# controller10.net
KiCad netlist of a schematic drawn in EAGLE
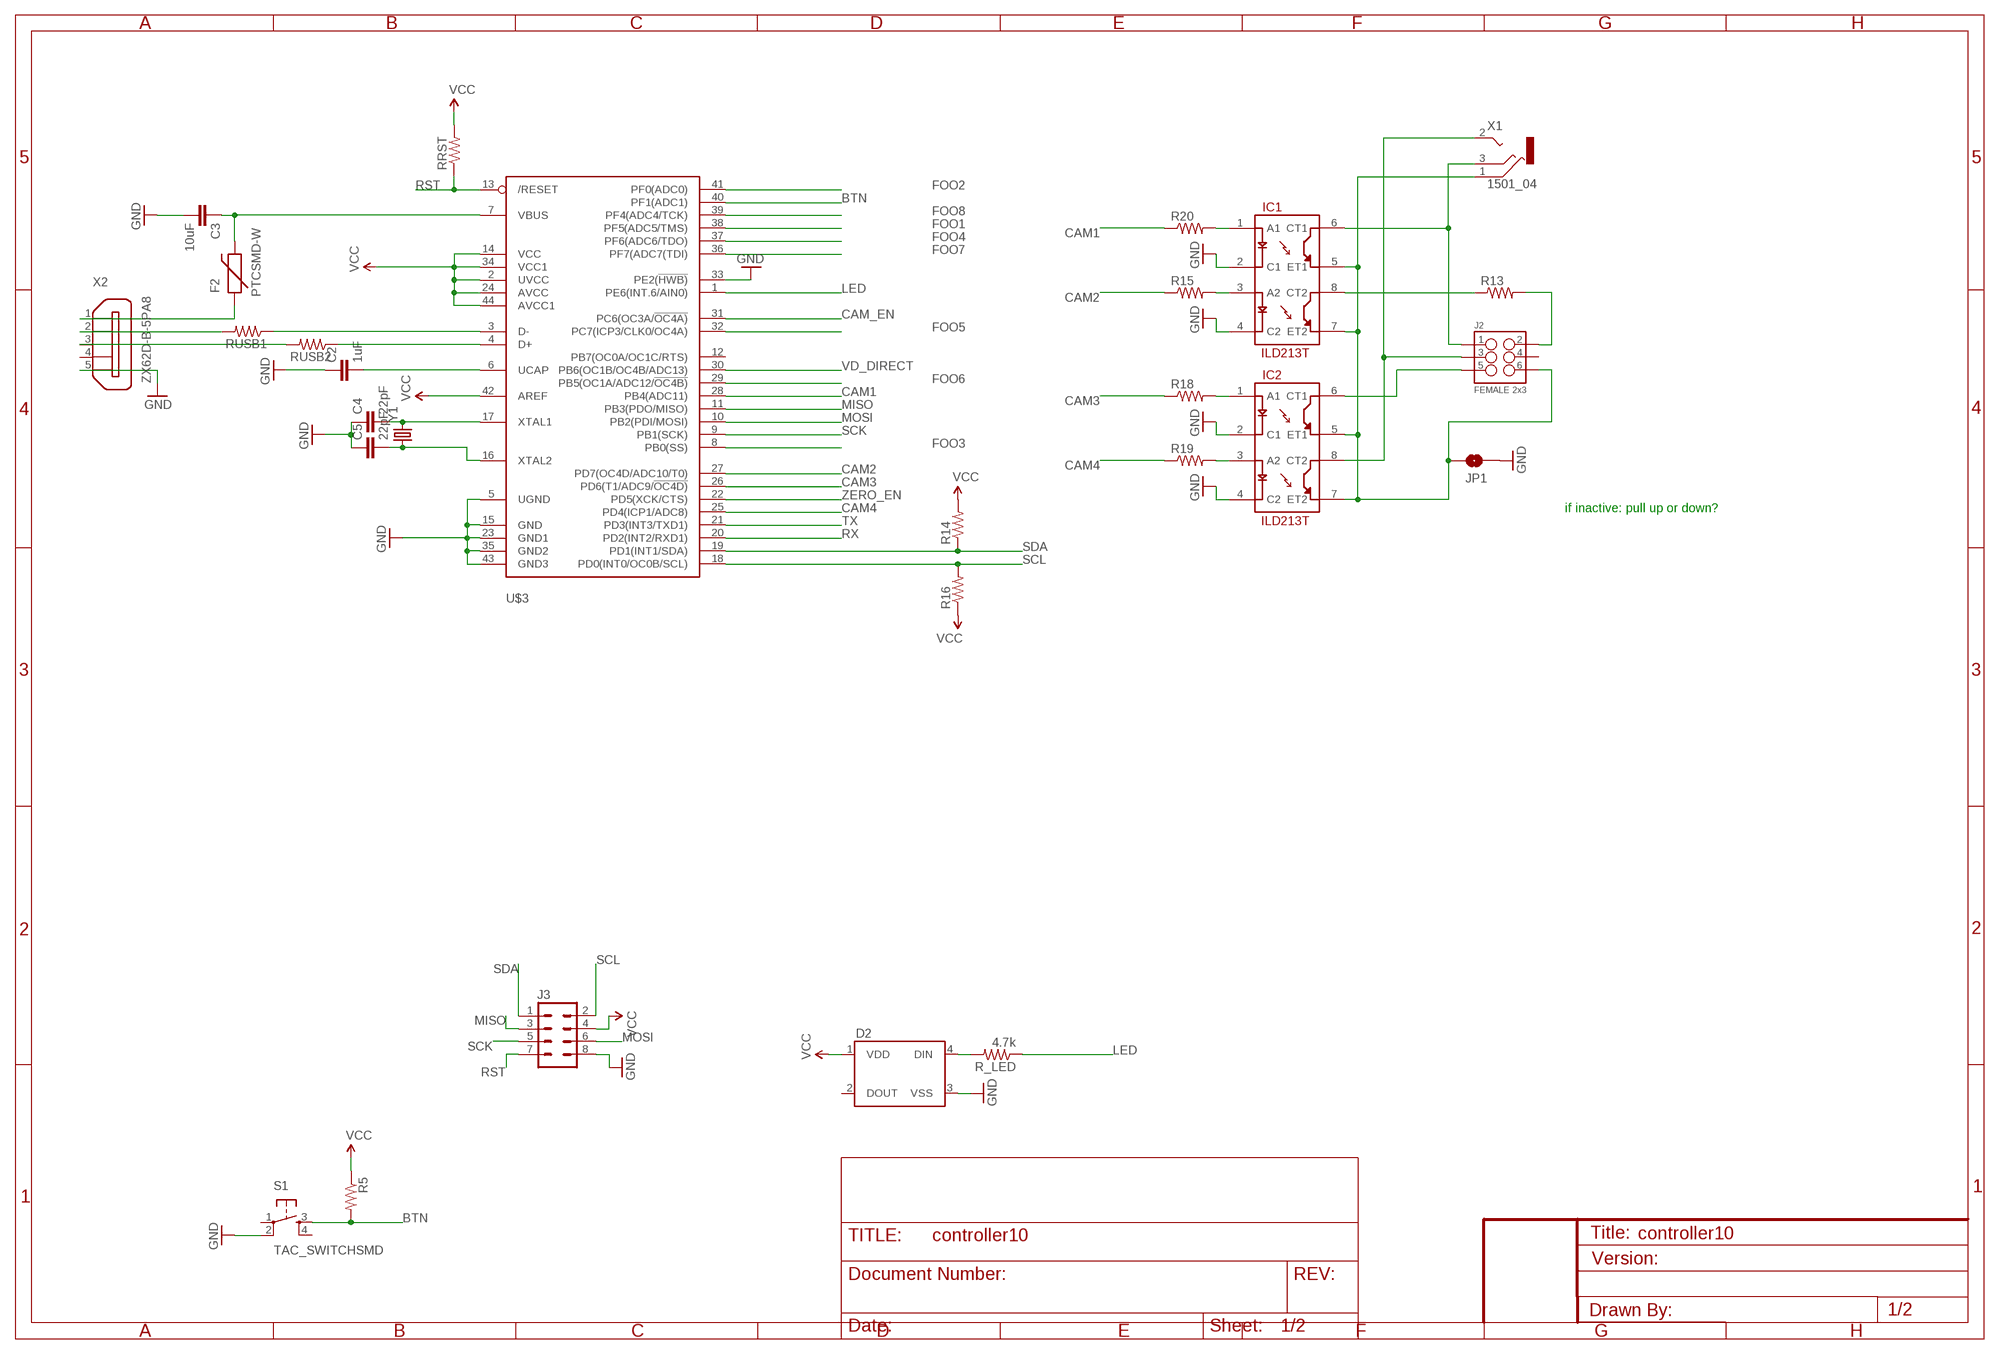
[diagram p0: schematic, sheet 1]
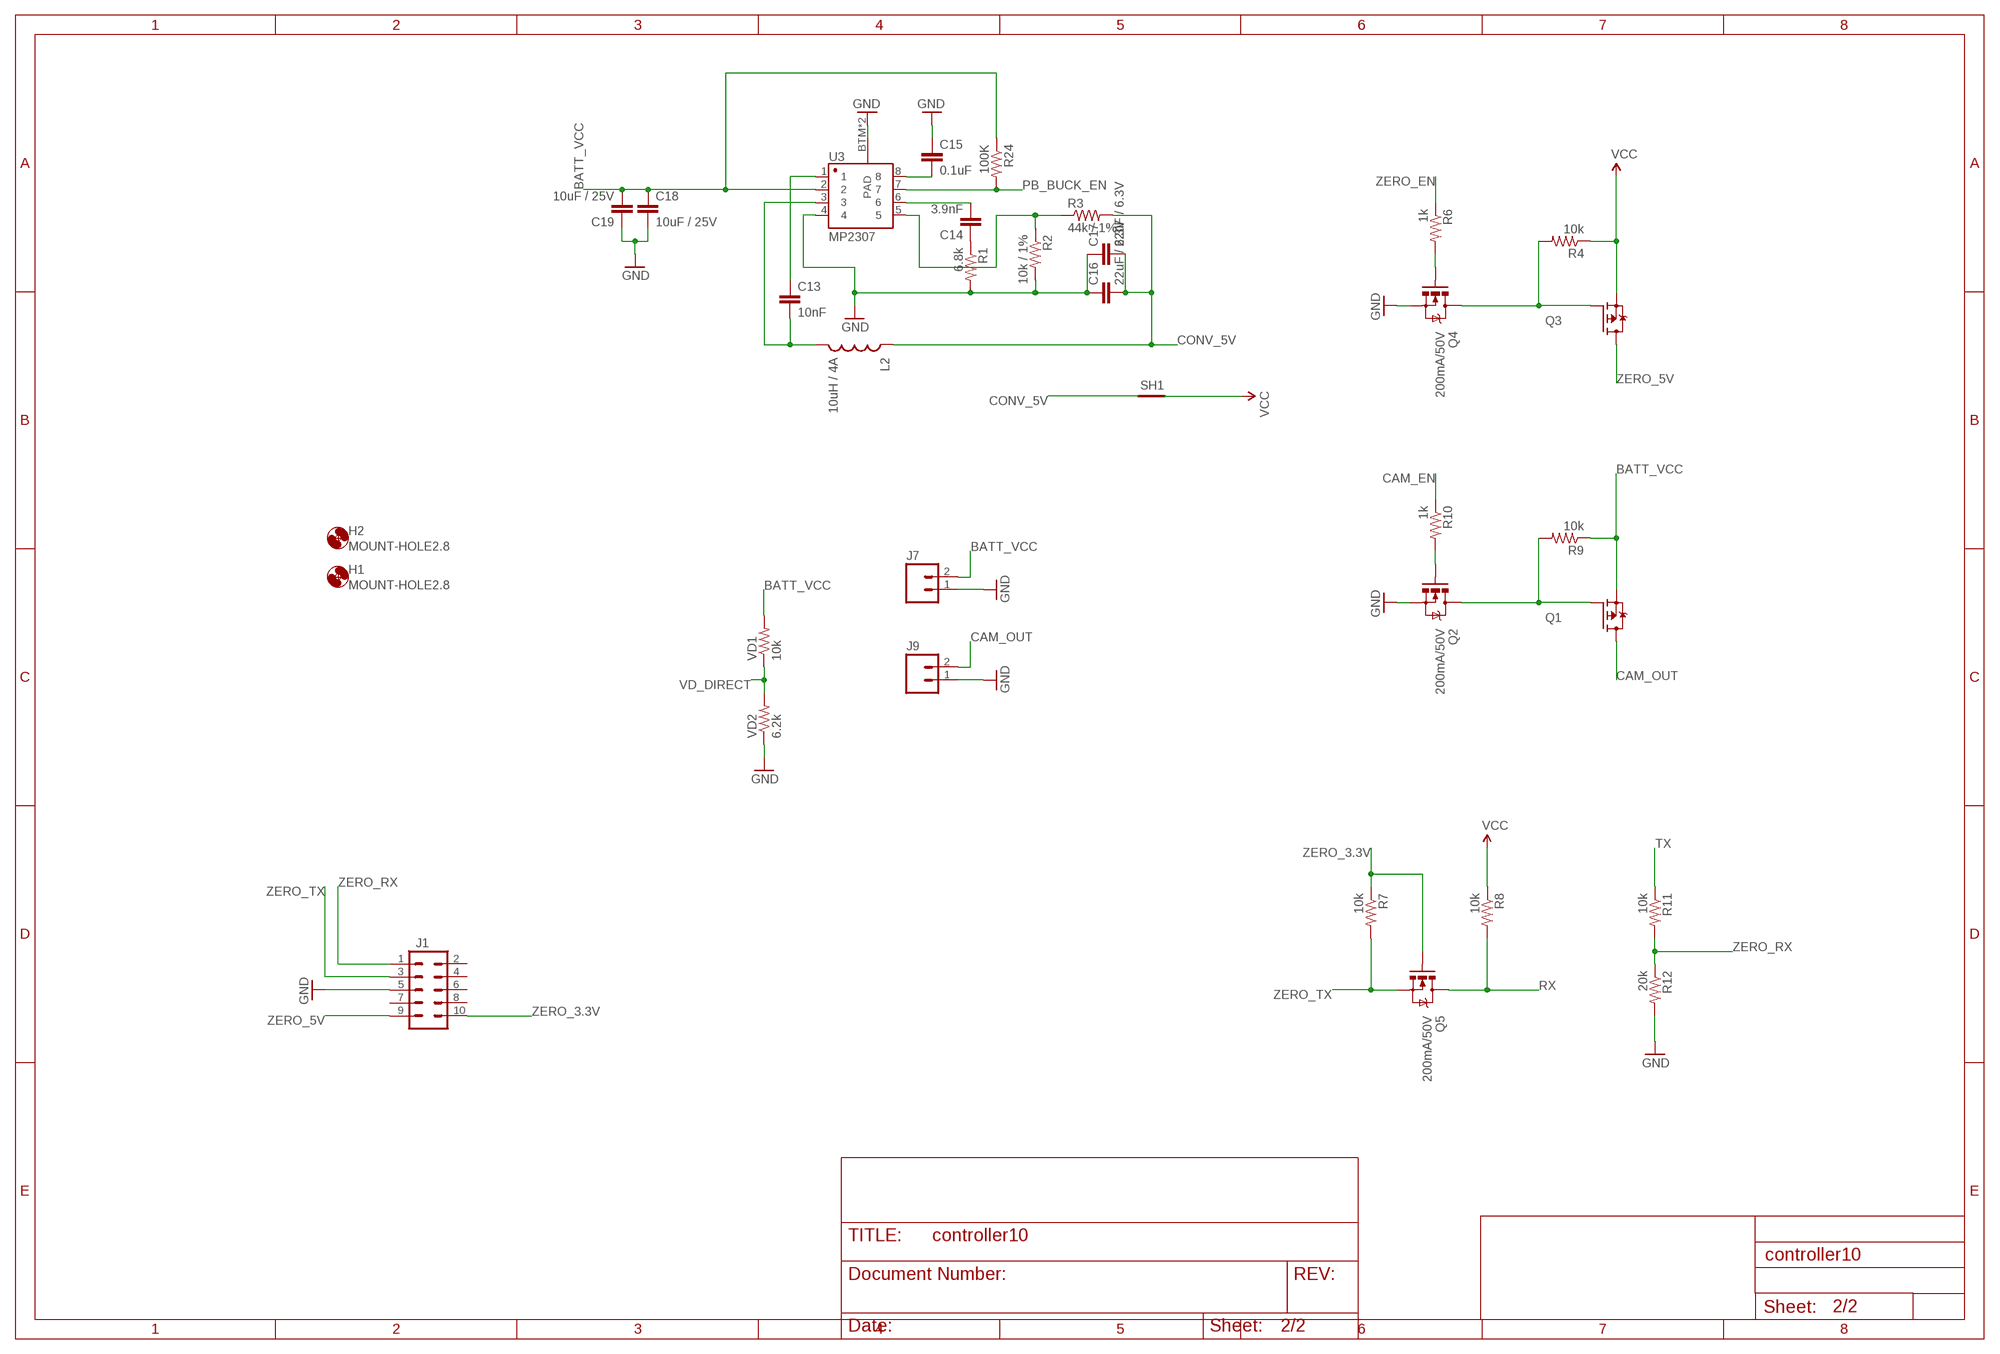
[diagram p1: schematic, sheet 2]

(export (version "E")
  (design (tool "Eeschema 10.0.6"))
  (components
    (comp (ref "C13")
      (value "10nF")
      (footprint "eagle-import:1206")
      (libsource (lib "eagle-import") (part "CAP1206"))
    )
    (comp (ref "C14")
      (value "3.9nF")
      (footprint "eagle-import:0805")
      (libsource (lib "eagle-import") (part "CAP0805"))
    )
    (comp (ref "C15")
      (value "0.1uF")
      (footprint "eagle-import:0805")
      (libsource (lib "eagle-import") (part "CAP0805"))
    )
    (comp (ref "C16")
      (value "22uF / 6.3V")
      (footprint "eagle-import:1210")
      (libsource (lib "eagle-import") (part "CAP1210"))
    )
    (comp (ref "C17")
      (value "22uF / 6.3V")
      (footprint "eagle-import:1210")
      (libsource (lib "eagle-import") (part "CAP1210"))
    )
    (comp (ref "C18")
      (value "10uF / 25V")
      (footprint "eagle-import:1210")
      (libsource (lib "eagle-import") (part "CAP1210"))
    )
    (comp (ref "C19")
      (value "10uF / 25V")
      (footprint "eagle-import:1210")
      (libsource (lib "eagle-import") (part "CAP1210"))
    )
    (comp (ref "H1")
      (value "MOUNT-HOLE2.8")
      (footprint "eagle-import:2,8")
      (libsource (lib "eagle-import") (part "MOUNT-HOLE2.8"))
    )
    (comp (ref "H2")
      (value "MOUNT-HOLE2.8")
      (footprint "eagle-import:2,8")
      (libsource (lib "eagle-import") (part "MOUNT-HOLE2.8"))
    )
    (comp (ref "J1")
      (value "M05X2PTH")
      (footprint "eagle-import:AVR_ICSP")
      (libsource (lib "eagle-import") (part "M05X2PTH"))
    )
    (comp (ref "J7")
      (value "M02LOCK")
      (footprint "eagle-import:1X02_LOCK")
      (libsource (lib "eagle-import") (part "M02LOCK"))
    )
    (comp (ref "J9")
      (value "M02LOCK")
      (footprint "eagle-import:1X02_LOCK")
      (libsource (lib "eagle-import") (part "M02LOCK"))
    )
    (comp (ref "L2")
      (value "10uH / 4A")
      (footprint "eagle-import:SRU1038")
      (libsource (lib "eagle-import") (part "INDUCTORSRU1038"))
    )
    (comp (ref "Q1")
      (value "FDD4141TO252")
      (footprint "eagle-import:TO252")
      (libsource (lib "eagle-import") (part "FDD4141TO252"))
    )
    (comp (ref "Q2")
      (value "200mA/50V")
      (footprint "eagle-import:SOT23-3")
      (libsource (lib "eagle-import") (part "MOSFET-NCHANNELBSS138"))
    )
    (comp (ref "Q3")
      (value "FDD4141TO252")
      (footprint "eagle-import:TO252")
      (libsource (lib "eagle-import") (part "FDD4141TO252"))
    )
    (comp (ref "Q4")
      (value "200mA/50V")
      (footprint "eagle-import:SOT23-3")
      (libsource (lib "eagle-import") (part "MOSFET-NCHANNELBSS138"))
    )
    (comp (ref "Q5")
      (value "200mA/50V")
      (footprint "eagle-import:SOT23-3")
      (libsource (lib "eagle-import") (part "MOSFET-NCHANNELBSS138"))
    )
    (comp (ref "R1")
      (value "6.8k")
      (footprint "eagle-import:0805")
      (libsource (lib "eagle-import") (part "SparkFun-Resistors_RESISTOR0805-RES"))
    )
    (comp (ref "R2")
      (value "10k / 1%")
      (footprint "eagle-import:0805")
      (libsource (lib "eagle-import") (part "SparkFun-Resistors_RESISTOR0805-RES"))
    )
    (comp (ref "R3")
      (value "44k / 1%")
      (footprint "eagle-import:0805")
      (libsource (lib "eagle-import") (part "SparkFun-Resistors_RESISTOR0805-RES"))
    )
    (comp (ref "R4")
      (value "10k")
      (footprint "eagle-import:0805")
      (libsource (lib "eagle-import") (part "SparkFun-Resistors_RESISTOR0805-RES"))
    )
    (comp (ref "R6")
      (value "1k")
      (footprint "eagle-import:0805")
      (libsource (lib "eagle-import") (part "SparkFun-Resistors_RESISTOR0805-RES"))
    )
    (comp (ref "R7")
      (value "10k")
      (footprint "eagle-import:0805")
      (libsource (lib "eagle-import") (part "SparkFun-Resistors_RESISTOR0805-RES"))
    )
    (comp (ref "R8")
      (value "10k")
      (footprint "eagle-import:0805")
      (libsource (lib "eagle-import") (part "SparkFun-Resistors_RESISTOR0805-RES"))
    )
    (comp (ref "R9")
      (value "10k")
      (footprint "eagle-import:0805")
      (libsource (lib "eagle-import") (part "SparkFun-Resistors_RESISTOR0805-RES"))
    )
    (comp (ref "R10")
      (value "1k")
      (footprint "eagle-import:0805")
      (libsource (lib "eagle-import") (part "SparkFun-Resistors_RESISTOR0805-RES"))
    )
    (comp (ref "R11")
      (value "10k")
      (footprint "eagle-import:0805")
      (libsource (lib "eagle-import") (part "SparkFun-Resistors_RESISTOR0805-RES"))
    )
    (comp (ref "R12")
      (value "20k")
      (footprint "eagle-import:0805")
      (libsource (lib "eagle-import") (part "SparkFun-Resistors_RESISTOR0805-RES"))
    )
    (comp (ref "R24")
      (value "100K")
      (footprint "eagle-import:0805")
      (libsource (lib "eagle-import") (part "SparkFun-Resistors_RESISTOR0805-RES"))
    )
    (comp (ref "SH1")
      (value "SHORT-HT5")
      (footprint "eagle-import:SHORT_TOP-50")
      (libsource (lib "eagle-import") (part "SHORT-HT5"))
    )
    (comp (ref "U3")
      (value "MP2307")
      (footprint "eagle-import:SO08")
      (libsource (lib "eagle-import") (part "GENERIC-SOIC8MSGEQ7N-FILTER"))
    )
    (comp (ref "VD1")
      (value "10k")
      (footprint "eagle-import:1206")
      (libsource (lib "eagle-import") (part "RESISTOR1206"))
    )
    (comp (ref "VD2")
      (value "6.2k")
      (footprint "eagle-import:1206")
      (libsource (lib "eagle-import") (part "RESISTOR1206"))
    )
    (comp (ref "C2")
      (value "1uF")
      (footprint "eagle-import:1206")
      (libsource (lib "eagle-import") (part "CAP1206"))
    )
    (comp (ref "C3")
      (value "10uF")
      (footprint "eagle-import:1206")
      (libsource (lib "eagle-import") (part "SparkFun-Passives_CAP1206"))
    )
    (comp (ref "C4")
      (value "22pF")
      (footprint "eagle-import:0805")
      (libsource (lib "eagle-import") (part "SparkFun-Passives_CAP0805"))
    )
    (comp (ref "C5")
      (value "22pF")
      (footprint "eagle-import:0805")
      (libsource (lib "eagle-import") (part "SparkFun-Passives_CAP0805"))
    )
    (comp (ref "D2")
      (value "WS2812B")
      (footprint "eagle-import:WS2812B")
      (libsource (lib "eagle-import") (part "WS2812B"))
    )
    (comp (ref "F2")
      (value "PTCSMD-W")
      (footprint "eagle-import:PTC-1206-WIDE")
      (libsource (lib "eagle-import") (part "PTCSMD-W"))
    )
    (comp (ref "IC1")
      (value "ILD213T")
      (footprint "eagle-import:SO08")
      (libsource (lib "eagle-import") (part "ILD213T"))
    )
    (comp (ref "IC2")
      (value "ILD213T")
      (footprint "eagle-import:SO08")
      (libsource (lib "eagle-import") (part "ILD213T"))
    )
    (comp (ref "J2")
      (value "FEMALE 2x3")
      (footprint "eagle-import:2X3")
      (libsource (lib "eagle-import") (part "M03X2FEMALE"))
    )
    (comp (ref "J3")
      (value "M04X2")
      (footprint "eagle-import:2X4")
      (libsource (lib "eagle-import") (part "M04X2"))
    )
    (comp (ref "JP1")
      (value "JUMPER-PAD-2-NOYES_SILK")
      (footprint "eagle-import:PAD-JUMPER-2-NO_YES_SILK")
      (libsource (lib "eagle-import") (part "JUMPER-PAD-2-NOYES_SILK"))
    )
    (comp (ref "R5")
      (value "RESISTOR1206")
      (footprint "eagle-import:1206")
      (libsource (lib "eagle-import") (part "RESISTOR1206"))
    )
    (comp (ref "R13")
      (value "RESISTOR0805-RES")
      (footprint "eagle-import:0805")
      (libsource (lib "eagle-import") (part "RESISTOR0805-RES"))
    )
    (comp (ref "R14")
      (value "RESISTOR0805-RES")
      (footprint "eagle-import:0805")
      (libsource (lib "eagle-import") (part "RESISTOR0805-RES"))
    )
    (comp (ref "R15")
      (value "RESISTOR0805-RES")
      (footprint "eagle-import:0805")
      (libsource (lib "eagle-import") (part "RESISTOR0805-RES"))
    )
    (comp (ref "R16")
      (value "RESISTOR0805-RES")
      (footprint "eagle-import:0805")
      (libsource (lib "eagle-import") (part "RESISTOR0805-RES"))
    )
    (comp (ref "R18")
      (value "RESISTOR0805-RES")
      (footprint "eagle-import:0805")
      (libsource (lib "eagle-import") (part "RESISTOR0805-RES"))
    )
    (comp (ref "R19")
      (value "RESISTOR0805-RES")
      (footprint "eagle-import:0805")
      (libsource (lib "eagle-import") (part "RESISTOR0805-RES"))
    )
    (comp (ref "R20")
      (value "RESISTOR0805-RES")
      (footprint "eagle-import:0805")
      (libsource (lib "eagle-import") (part "RESISTOR0805-RES"))
    )
    (comp (ref "RRST")
      (value "RESISTOR1206")
      (footprint "eagle-import:1206")
      (libsource (lib "eagle-import") (part "RESISTOR1206"))
    )
    (comp (ref "RUSB1")
      (value "RESISTOR1206")
      (footprint "eagle-import:1206")
      (libsource (lib "eagle-import") (part "RESISTOR1206"))
    )
    (comp (ref "RUSB2")
      (value "RESISTOR1206")
      (footprint "eagle-import:1206")
      (libsource (lib "eagle-import") (part "RESISTOR1206"))
    )
    (comp (ref "R_LED")
      (value "4.7k")
      (footprint "eagle-import:1206")
      (libsource (lib "eagle-import") (part "SparkFun-Resistors_RESISTOR1206"))
    )
    (comp (ref "S1")
      (value "TAC_SWITCHSMD")
      (footprint "eagle-import:TACTILE-PTH")
      (libsource (lib "eagle-import") (part "TAC_SWITCHPTH"))
    )
    (comp (ref "U$3")
      (value "ATMEGA32U4-AU")
      (footprint "eagle-import:TQFP44")
      (libsource (lib "eagle-import") (part "ATMEGA32U4-AU"))
    )
    (comp (ref "X1")
      (value "1501_04")
      (footprint "eagle-import:1501_05")
      (libsource (lib "eagle-import") (part "1501_04"))
    )
    (comp (ref "X2")
      (value "ZX62D-B-5PA8")
      (footprint "eagle-import:ZX62D-B-5PA8")
      (fields (field (name "MF") "Hirose"))
      (libsource (lib "eagle-import") (part "ZX62D-B-5PA8"))
    )
    (comp (ref "Y1")
      (value "CRYSTALCRYSTAL-SMD-5X3-16MHZ")
      (footprint "eagle-import:CRYSTAL-SMD-5X3")
      (libsource (lib "eagle-import") (part "CRYSTALCRYSTAL-SMD-5X3-16MHZ"))
    )
  )
  (nets
    (net (code "1") (name "BATT_VCC") (class "Default")
      (node (ref "C18") (pin "1") (pinfunction "1_1") (pintype "passive"))
      (node (ref "C19") (pin "2") (pinfunction "2_2") (pintype "passive"))
      (node (ref "J7") (pin "2") (pinfunction "2_2") (pintype "passive"))
      (node (ref "Q1") (pin "2") (pinfunction "S_2") (pintype "passive"))
      (node (ref "R24") (pin "1") (pinfunction "1_1") (pintype "passive"))
      (node (ref "R9") (pin "1") (pinfunction "1_1") (pintype "passive"))
      (node (ref "U3") (pin "2") (pinfunction "2_2") (pintype "bidirectional"))
      (node (ref "VD1") (pin "2") (pinfunction "2_2") (pintype "passive"))
    )
    (net (code "2") (name "BTN") (class "Default")
      (node (ref "R5") (pin "2") (pinfunction "2_2") (pintype "passive"))
      (node (ref "S1") (pin "3") (pinfunction "3_3") (pintype "passive"))
      (node (ref "U$3") (pin "40") (pinfunction "PF1(ADC1)_40") (pintype "bidirectional"))
    )
    (net (code "3") (name "CAM1") (class "Default")
      (node (ref "R20") (pin "1") (pinfunction "1_1") (pintype "passive"))
      (node (ref "U$3") (pin "28") (pinfunction "PB4(ADC11)_28") (pintype "bidirectional"))
    )
    (net (code "4") (name "CAM2") (class "Default")
      (node (ref "R15") (pin "1") (pinfunction "1_1") (pintype "passive"))
      (node (ref "U$3") (pin "27") (pinfunction "PD7(OC4D/ADC10/T0)_27") (pintype "bidirectional"))
    )
    (net (code "5") (name "CAM3") (class "Default")
      (node (ref "R18") (pin "1") (pinfunction "1_1") (pintype "passive"))
      (node (ref "U$3") (pin "26") (pinfunction "PD6(T1/ADC9/~{OC4D})_26") (pintype "bidirectional"))
    )
    (net (code "6") (name "CAM4") (class "Default")
      (node (ref "R19") (pin "1") (pinfunction "1_1") (pintype "passive"))
      (node (ref "U$3") (pin "25") (pinfunction "PD4(ICP1/ADC8)_25") (pintype "bidirectional"))
    )
    (net (code "7") (name "CAM_EN") (class "Default")
      (node (ref "R10") (pin "1") (pinfunction "1_1") (pintype "passive"))
      (node (ref "U$3") (pin "31") (pinfunction "PC6(OC3A/~{OC4A})_31") (pintype "bidirectional"))
    )
    (net (code "8") (name "CAM_OUT") (class "Default")
      (node (ref "J9") (pin "2") (pinfunction "2_2") (pintype "passive"))
      (node (ref "Q1") (pin "3") (pinfunction "D_3") (pintype "passive"))
    )
    (net (code "9") (name "CONV_5V") (class "Default")
      (node (ref "C16") (pin "2") (pinfunction "2_2") (pintype "passive"))
      (node (ref "C17") (pin "2") (pinfunction "2_2") (pintype "passive"))
      (node (ref "L2") (pin "1") (pinfunction "1_1") (pintype "passive"))
      (node (ref "R3") (pin "2") (pinfunction "2_2") (pintype "passive"))
      (node (ref "SH1") (pin "1") (pinfunction "P$1_1") (pintype "bidirectional"))
    )
    (net (code "10") (name "FOO1") (class "Default")
      (node (ref "U$3") (pin "38") (pinfunction "PF5(ADC5/TMS)_38") (pintype "bidirectional"))
    )
    (net (code "11") (name "FOO2") (class "Default")
      (node (ref "U$3") (pin "41") (pinfunction "PF0(ADC0)_41") (pintype "bidirectional"))
    )
    (net (code "12") (name "FOO3") (class "Default")
      (node (ref "U$3") (pin "8") (pinfunction "PB0(SS)_8") (pintype "bidirectional"))
    )
    (net (code "13") (name "FOO4") (class "Default")
      (node (ref "U$3") (pin "37") (pinfunction "PF6(ADC6/TDO)_37") (pintype "bidirectional"))
    )
    (net (code "14") (name "FOO5") (class "Default")
      (node (ref "U$3") (pin "32") (pinfunction "PC7(ICP3/CLK0/OC4A)_32") (pintype "bidirectional"))
    )
    (net (code "15") (name "FOO6") (class "Default")
      (node (ref "U$3") (pin "29") (pinfunction "PB5(OC1A/ADC12/~{OC4B})_29") (pintype "bidirectional"))
    )
    (net (code "16") (name "FOO7") (class "Default")
      (node (ref "U$3") (pin "36") (pinfunction "PF7(ADC7(TDI)_36") (pintype "bidirectional"))
    )
    (net (code "17") (name "FOO8") (class "Default")
      (node (ref "U$3") (pin "39") (pinfunction "PF4(ADC4/TCK)_39") (pintype "bidirectional"))
    )
    (net (code "18") (name "GND") (class "Default")
      (node (ref "C15") (pin "1") (pinfunction "1_1") (pintype "passive"))
      (node (ref "C16") (pin "1") (pinfunction "1_1") (pintype "passive"))
      (node (ref "C17") (pin "1") (pinfunction "1_1") (pintype "passive"))
      (node (ref "C18") (pin "2") (pinfunction "2_2") (pintype "passive"))
      (node (ref "C19") (pin "1") (pinfunction "1_1") (pintype "passive"))
      (node (ref "C2") (pin "1") (pinfunction "1_1") (pintype "passive"))
      (node (ref "C3") (pin "2") (pinfunction "2_2") (pintype "passive"))
      (node (ref "C4") (pin "1") (pinfunction "1_1") (pintype "passive"))
      (node (ref "C5") (pin "1") (pinfunction "1_1") (pintype "passive"))
      (node (ref "D2") (pin "3") (pinfunction "VSS_3") (pintype "power_in"))
      (node (ref "IC1") (pin "2") (pinfunction "C1_2") (pintype "bidirectional"))
      (node (ref "IC1") (pin "4") (pinfunction "C2_4") (pintype "bidirectional"))
      (node (ref "IC2") (pin "2") (pinfunction "C1_2") (pintype "bidirectional"))
      (node (ref "IC2") (pin "4") (pinfunction "C2_4") (pintype "bidirectional"))
      (node (ref "J1") (pin "5") (pinfunction "5_5") (pintype "passive"))
      (node (ref "J3") (pin "8") (pinfunction "8_8") (pintype "passive"))
      (node (ref "J7") (pin "1") (pinfunction "1_1") (pintype "passive"))
      (node (ref "J9") (pin "1") (pinfunction "1_1") (pintype "passive"))
      (node (ref "JP1") (pin "1") (pinfunction "1_1") (pintype "passive"))
      (node (ref "Q2") (pin "2") (pinfunction "S_2") (pintype "passive"))
      (node (ref "Q4") (pin "2") (pinfunction "S_2") (pintype "passive"))
      (node (ref "R1") (pin "2") (pinfunction "2_2") (pintype "passive"))
      (node (ref "R12") (pin "2") (pinfunction "2_2") (pintype "passive"))
      (node (ref "R2") (pin "2") (pinfunction "2_2") (pintype "passive"))
      (node (ref "S1") (pin "2") (pinfunction "2_2") (pintype "passive"))
      (node (ref "U$3") (pin "15") (pinfunction "GND_15") (pintype "bidirectional"))
      (node (ref "U$3") (pin "23") (pinfunction "GND1_23") (pintype "bidirectional"))
      (node (ref "U$3") (pin "33") (pinfunction "PE2(~{HWB})_33") (pintype "bidirectional"))
      (node (ref "U$3") (pin "35") (pinfunction "GND2_35") (pintype "bidirectional"))
      (node (ref "U$3") (pin "43") (pinfunction "GND3_43") (pintype "bidirectional"))
      (node (ref "U$3") (pin "5") (pinfunction "UGND_5") (pintype "bidirectional"))
      (node (ref "U3") (pin "4") (pinfunction "4_4") (pintype "bidirectional"))
      (node (ref "U3") (pin "BTM") (pinfunction "PAD_BTM") (pintype "bidirectional"))
      (node (ref "U3") (pin "P$1") (pinfunction "PAD_P$1") (pintype "bidirectional"))
      (node (ref "VD2") (pin "1") (pinfunction "1_1") (pintype "passive"))
      (node (ref "X2") (pin "5") (pinfunction "5_5") (pintype "passive"))
    )
    (net (code "19") (name "LED") (class "Default")
      (node (ref "R_LED") (pin "1") (pinfunction "1_1") (pintype "passive"))
      (node (ref "U$3") (pin "1") (pinfunction "PE6(INT.6/AIN0)_1") (pintype "bidirectional"))
    )
    (net (code "20") (name "MISO") (class "Default")
      (node (ref "J3") (pin "3") (pinfunction "3_3") (pintype "passive"))
      (node (ref "U$3") (pin "11") (pinfunction "PB3(PDO/MISO)_11") (pintype "bidirectional"))
    )
    (net (code "21") (name "MOSI") (class "Default")
      (node (ref "J3") (pin "6") (pinfunction "6_6") (pintype "passive"))
      (node (ref "U$3") (pin "10") (pinfunction "PB2(PDI/MOSI)_10") (pintype "bidirectional"))
    )
    (net (code "22") (name "Net-(C13-Pad1)") (class "Default")
      (node (ref "C13") (pin "1") (pinfunction "1_1") (pintype "passive"))
      (node (ref "U3") (pin "1") (pinfunction "1_1") (pintype "bidirectional"))
    )
    (net (code "23") (name "Net-(C13-Pad2)") (class "Default")
      (node (ref "C13") (pin "2") (pinfunction "2_2") (pintype "passive"))
      (node (ref "L2") (pin "2") (pinfunction "2_2") (pintype "passive"))
      (node (ref "U3") (pin "3") (pinfunction "3_3") (pintype "bidirectional"))
    )
    (net (code "24") (name "Net-(C14-Pad1)") (class "Default")
      (node (ref "C14") (pin "1") (pinfunction "1_1") (pintype "passive"))
      (node (ref "R1") (pin "1") (pinfunction "1_1") (pintype "passive"))
    )
    (net (code "25") (name "Net-(C14-Pad2)") (class "Default")
      (node (ref "C14") (pin "2") (pinfunction "2_2") (pintype "passive"))
      (node (ref "U3") (pin "6") (pinfunction "6_6") (pintype "bidirectional"))
    )
    (net (code "26") (name "Net-(C15-Pad2)") (class "Default")
      (node (ref "C15") (pin "2") (pinfunction "2_2") (pintype "passive"))
      (node (ref "U3") (pin "8") (pinfunction "8_8") (pintype "bidirectional"))
    )
    (net (code "27") (name "Net-(D2-DIN)") (class "Default")
      (node (ref "D2") (pin "4") (pinfunction "DIN_4") (pintype "input"))
      (node (ref "R_LED") (pin "2") (pinfunction "2_2") (pintype "passive"))
    )
    (net (code "28") (name "Net-(F2-Pad1)") (class "Default")
      (node (ref "F2") (pin "1") (pinfunction "1_1") (pintype "bidirectional"))
      (node (ref "X2") (pin "1") (pinfunction "1_1") (pintype "passive"))
    )
    (net (code "29") (name "Net-(IC1-A1)") (class "Default")
      (node (ref "IC1") (pin "1") (pinfunction "A1_1") (pintype "bidirectional"))
      (node (ref "R20") (pin "2") (pinfunction "2_2") (pintype "passive"))
    )
    (net (code "30") (name "Net-(IC1-A2)") (class "Default")
      (node (ref "IC1") (pin "3") (pinfunction "A2_3") (pintype "bidirectional"))
      (node (ref "R15") (pin "2") (pinfunction "2_2") (pintype "passive"))
    )
    (net (code "31") (name "Net-(IC1-CT1)") (class "Default")
      (node (ref "IC1") (pin "6") (pinfunction "CT1_6") (pintype "bidirectional"))
      (node (ref "J2") (pin "1") (pinfunction "1_1") (pintype "bidirectional"))
      (node (ref "X1") (pin "3") (pinfunction "3_3") (pintype "passive"))
    )
    (net (code "32") (name "Net-(IC1-CT2)") (class "Default")
      (node (ref "IC1") (pin "8") (pinfunction "CT2_8") (pintype "bidirectional"))
      (node (ref "R13") (pin "1") (pinfunction "1_1") (pintype "passive"))
    )
    (net (code "33") (name "Net-(IC1-ET1)") (class "Default")
      (node (ref "IC1") (pin "5") (pinfunction "ET1_5") (pintype "bidirectional"))
      (node (ref "IC1") (pin "7") (pinfunction "ET2_7") (pintype "bidirectional"))
      (node (ref "IC2") (pin "5") (pinfunction "ET1_5") (pintype "bidirectional"))
      (node (ref "IC2") (pin "7") (pinfunction "ET2_7") (pintype "bidirectional"))
      (node (ref "J2") (pin "6") (pinfunction "6_6") (pintype "bidirectional"))
      (node (ref "JP1") (pin "2") (pinfunction "2_2") (pintype "passive"))
      (node (ref "X1") (pin "1") (pinfunction "1_1") (pintype "passive"))
    )
    (net (code "34") (name "Net-(IC2-A1)") (class "Default")
      (node (ref "IC2") (pin "1") (pinfunction "A1_1") (pintype "bidirectional"))
      (node (ref "R18") (pin "2") (pinfunction "2_2") (pintype "passive"))
    )
    (net (code "35") (name "Net-(IC2-A2)") (class "Default")
      (node (ref "IC2") (pin "3") (pinfunction "A2_3") (pintype "bidirectional"))
      (node (ref "R19") (pin "2") (pinfunction "2_2") (pintype "passive"))
    )
    (net (code "36") (name "Net-(IC2-CT1)") (class "Default")
      (node (ref "IC2") (pin "6") (pinfunction "CT1_6") (pintype "bidirectional"))
      (node (ref "J2") (pin "5") (pinfunction "5_5") (pintype "bidirectional"))
    )
    (net (code "37") (name "Net-(IC2-CT2)") (class "Default")
      (node (ref "IC2") (pin "8") (pinfunction "CT2_8") (pintype "bidirectional"))
      (node (ref "J2") (pin "3") (pinfunction "3_3") (pintype "bidirectional"))
      (node (ref "X1") (pin "2") (pinfunction "2_2") (pintype "passive"))
    )
    (net (code "38") (name "Net-(J2-Pad2)") (class "Default")
      (node (ref "J2") (pin "2") (pinfunction "2_2") (pintype "bidirectional"))
      (node (ref "R13") (pin "2") (pinfunction "2_2") (pintype "passive"))
    )
    (net (code "39") (name "Net-(Q1-G)") (class "Default")
      (node (ref "Q1") (pin "1") (pinfunction "G_1") (pintype "passive"))
      (node (ref "Q2") (pin "3") (pinfunction "D_3") (pintype "passive"))
      (node (ref "R9") (pin "2") (pinfunction "2_2") (pintype "passive"))
    )
    (net (code "40") (name "Net-(Q2-G)") (class "Default")
      (node (ref "Q2") (pin "1") (pinfunction "G_1") (pintype "passive"))
      (node (ref "R10") (pin "2") (pinfunction "2_2") (pintype "passive"))
    )
    (net (code "41") (name "Net-(Q3-G)") (class "Default")
      (node (ref "Q3") (pin "1") (pinfunction "G_1") (pintype "passive"))
      (node (ref "Q4") (pin "3") (pinfunction "D_3") (pintype "passive"))
      (node (ref "R4") (pin "2") (pinfunction "2_2") (pintype "passive"))
    )
    (net (code "42") (name "Net-(Q4-G)") (class "Default")
      (node (ref "Q4") (pin "1") (pinfunction "G_1") (pintype "passive"))
      (node (ref "R6") (pin "2") (pinfunction "2_2") (pintype "passive"))
    )
    (net (code "43") (name "Net-(R2-Pad1)") (class "Default")
      (node (ref "R2") (pin "1") (pinfunction "1_1") (pintype "passive"))
      (node (ref "R3") (pin "1") (pinfunction "1_1") (pintype "passive"))
      (node (ref "U3") (pin "5") (pinfunction "5_5") (pintype "bidirectional"))
    )
    (net (code "44") (name "Net-(RUSB1-Pad2)") (class "Default")
      (node (ref "RUSB1") (pin "2") (pinfunction "2_2") (pintype "passive"))
      (node (ref "X2") (pin "2") (pinfunction "2_2") (pintype "passive"))
    )
    (net (code "45") (name "Net-(RUSB2-Pad2)") (class "Default")
      (node (ref "RUSB2") (pin "2") (pinfunction "2_2") (pintype "passive"))
      (node (ref "X2") (pin "3") (pinfunction "3_3") (pintype "passive"))
    )
    (net (code "46") (name "Net-(U$3-D+)") (class "Default")
      (node (ref "RUSB2") (pin "1") (pinfunction "1_1") (pintype "passive"))
      (node (ref "U$3") (pin "4") (pinfunction "D+_4") (pintype "bidirectional"))
    )
    (net (code "47") (name "Net-(U$3-D-)") (class "Default")
      (node (ref "RUSB1") (pin "1") (pinfunction "1_1") (pintype "passive"))
      (node (ref "U$3") (pin "3") (pinfunction "D-_3") (pintype "bidirectional"))
    )
    (net (code "48") (name "Net-(U$3-UCAP)") (class "Default")
      (node (ref "C2") (pin "2") (pinfunction "2_2") (pintype "passive"))
      (node (ref "U$3") (pin "6") (pinfunction "UCAP_6") (pintype "bidirectional"))
    )
    (net (code "49") (name "Net-(U$3-VBUS)") (class "Default")
      (node (ref "C3") (pin "1") (pinfunction "1_1") (pintype "passive"))
      (node (ref "F2") (pin "2") (pinfunction "2_2") (pintype "bidirectional"))
      (node (ref "U$3") (pin "7") (pinfunction "VBUS_7") (pintype "bidirectional"))
    )
    (net (code "50") (name "Net-(U$3-XTAL1)") (class "Default")
      (node (ref "C4") (pin "2") (pinfunction "2_2") (pintype "passive"))
      (node (ref "U$3") (pin "17") (pinfunction "XTAL1_17") (pintype "bidirectional"))
      (node (ref "Y1") (pin "3") (pinfunction "2_3") (pintype "passive"))
    )
    (net (code "51") (name "Net-(U$3-XTAL2)") (class "Default")
      (node (ref "C5") (pin "2") (pinfunction "2_2") (pintype "passive"))
      (node (ref "U$3") (pin "16") (pinfunction "XTAL2_16") (pintype "bidirectional"))
      (node (ref "Y1") (pin "1") (pinfunction "1_1") (pintype "passive"))
    )
    (net (code "52") (name "PB_BUCK_EN") (class "Default")
      (node (ref "R24") (pin "2") (pinfunction "2_2") (pintype "passive"))
      (node (ref "U3") (pin "7") (pinfunction "7_7") (pintype "bidirectional"))
    )
    (net (code "53") (name "RST") (class "Default")
      (node (ref "J3") (pin "7") (pinfunction "7_7") (pintype "passive"))
      (node (ref "RRST") (pin "1") (pinfunction "1_1") (pintype "passive"))
      (node (ref "U$3") (pin "13") (pinfunction "/RESET_13") (pintype "bidirectional"))
    )
    (net (code "54") (name "RX") (class "Default")
      (node (ref "Q5") (pin "3") (pinfunction "D_3") (pintype "passive"))
      (node (ref "R8") (pin "2") (pinfunction "2_2") (pintype "passive"))
      (node (ref "U$3") (pin "20") (pinfunction "PD2(INT2/RXD1)_20") (pintype "bidirectional"))
    )
    (net (code "55") (name "SCK") (class "Default")
      (node (ref "J3") (pin "5") (pinfunction "5_5") (pintype "passive"))
      (node (ref "U$3") (pin "9") (pinfunction "PB1(SCK)_9") (pintype "bidirectional"))
    )
    (net (code "56") (name "SCL") (class "Default")
      (node (ref "J3") (pin "2") (pinfunction "2_2") (pintype "passive"))
      (node (ref "R16") (pin "2") (pinfunction "2_2") (pintype "passive"))
      (node (ref "U$3") (pin "18") (pinfunction "PD0(INT0/OC0B/SCL)_18") (pintype "bidirectional"))
    )
    (net (code "57") (name "SDA") (class "Default")
      (node (ref "J3") (pin "1") (pinfunction "1_1") (pintype "passive"))
      (node (ref "R14") (pin "1") (pinfunction "1_1") (pintype "passive"))
      (node (ref "U$3") (pin "19") (pinfunction "PD1(INT1/SDA)_19") (pintype "bidirectional"))
    )
    (net (code "58") (name "TX") (class "Default")
      (node (ref "R11") (pin "1") (pinfunction "1_1") (pintype "passive"))
      (node (ref "U$3") (pin "21") (pinfunction "PD3(INT3/TXD1)_21") (pintype "bidirectional"))
    )
    (net (code "59") (name "VCC") (class "Default")
      (node (ref "D2") (pin "1") (pinfunction "VDD_1") (pintype "power_in"))
      (node (ref "J3") (pin "4") (pinfunction "4_4") (pintype "passive"))
      (node (ref "Q3") (pin "2") (pinfunction "S_2") (pintype "passive"))
      (node (ref "R14") (pin "2") (pinfunction "2_2") (pintype "passive"))
      (node (ref "R16") (pin "1") (pinfunction "1_1") (pintype "passive"))
      (node (ref "R4") (pin "1") (pinfunction "1_1") (pintype "passive"))
      (node (ref "R5") (pin "1") (pinfunction "1_1") (pintype "passive"))
      (node (ref "R8") (pin "1") (pinfunction "1_1") (pintype "passive"))
      (node (ref "RRST") (pin "2") (pinfunction "2_2") (pintype "passive"))
      (node (ref "SH1") (pin "2") (pinfunction "P$2_2") (pintype "bidirectional"))
      (node (ref "U$3") (pin "14") (pinfunction "VCC_14") (pintype "bidirectional"))
      (node (ref "U$3") (pin "2") (pinfunction "UVCC_2") (pintype "bidirectional"))
      (node (ref "U$3") (pin "24") (pinfunction "AVCC_24") (pintype "bidirectional"))
      (node (ref "U$3") (pin "34") (pinfunction "VCC1_34") (pintype "bidirectional"))
      (node (ref "U$3") (pin "42") (pinfunction "AREF_42") (pintype "bidirectional"))
      (node (ref "U$3") (pin "44") (pinfunction "AVCC1_44") (pintype "bidirectional"))
    )
    (net (code "60") (name "VD_DIRECT") (class "Default")
      (node (ref "U$3") (pin "30") (pinfunction "PB6(OC1B/OC4B/ADC13)_30") (pintype "bidirectional"))
      (node (ref "VD1") (pin "1") (pinfunction "1_1") (pintype "passive"))
      (node (ref "VD2") (pin "2") (pinfunction "2_2") (pintype "passive"))
    )
    (net (code "61") (name "ZERO_3.3V") (class "Default")
      (node (ref "J1") (pin "10") (pinfunction "10_10") (pintype "passive"))
      (node (ref "Q5") (pin "1") (pinfunction "G_1") (pintype "passive"))
      (node (ref "R7") (pin "1") (pinfunction "1_1") (pintype "passive"))
    )
    (net (code "62") (name "ZERO_5V") (class "Default")
      (node (ref "J1") (pin "9") (pinfunction "9_9") (pintype "passive"))
      (node (ref "Q3") (pin "3") (pinfunction "D_3") (pintype "passive"))
    )
    (net (code "63") (name "ZERO_EN") (class "Default")
      (node (ref "R6") (pin "1") (pinfunction "1_1") (pintype "passive"))
      (node (ref "U$3") (pin "22") (pinfunction "PD5(XCK/CTS)_22") (pintype "bidirectional"))
    )
    (net (code "64") (name "ZERO_RX") (class "Default")
      (node (ref "J1") (pin "1") (pinfunction "1_1") (pintype "passive"))
      (node (ref "R11") (pin "2") (pinfunction "2_2") (pintype "passive"))
      (node (ref "R12") (pin "1") (pinfunction "1_1") (pintype "passive"))
    )
    (net (code "65") (name "ZERO_TX") (class "Default")
      (node (ref "J1") (pin "3") (pinfunction "3_3") (pintype "passive"))
      (node (ref "Q5") (pin "2") (pinfunction "S_2") (pintype "passive"))
      (node (ref "R7") (pin "2") (pinfunction "2_2") (pintype "passive"))
    )
    (net (code "66") (name "unconnected-(D2-DOUT-Pad2)") (class "Default")
      (node (ref "D2") (pin "2") (pinfunction "DOUT_2") (pintype "output"))
    )
    (net (code "67") (name "unconnected-(J1-Pad2)") (class "Default")
      (node (ref "J1") (pin "2") (pinfunction "2_2") (pintype "passive"))
    )
    (net (code "68") (name "unconnected-(J1-Pad4)") (class "Default")
      (node (ref "J1") (pin "4") (pinfunction "4_4") (pintype "passive"))
    )
    (net (code "69") (name "unconnected-(J1-Pad6)") (class "Default")
      (node (ref "J1") (pin "6") (pinfunction "6_6") (pintype "passive"))
    )
    (net (code "70") (name "unconnected-(J1-Pad7)") (class "Default")
      (node (ref "J1") (pin "7") (pinfunction "7_7") (pintype "passive"))
    )
    (net (code "71") (name "unconnected-(J1-Pad8)") (class "Default")
      (node (ref "J1") (pin "8") (pinfunction "8_8") (pintype "passive"))
    )
    (net (code "72") (name "unconnected-(J2-Pad4)") (class "Default")
      (node (ref "J2") (pin "4") (pinfunction "4_4") (pintype "bidirectional"))
    )
    (net (code "73") (name "unconnected-(S1-Pad1)") (class "Default")
      (node (ref "S1") (pin "1") (pinfunction "1_1") (pintype "passive"))
    )
    (net (code "74") (name "unconnected-(S1-Pad4)") (class "Default")
      (node (ref "S1") (pin "4") (pinfunction "4_4") (pintype "passive"))
    )
    (net (code "75") (name "unconnected-(U$3-PB7(OC0A{slash}OC1C{slash}RTS)-Pad12)") (class "Default")
      (node (ref "U$3") (pin "12") (pinfunction "PB7(OC0A/OC1C/RTS)_12") (pintype "bidirectional"))
    )
    (net (code "76") (name "unconnected-(X2-Pad4)") (class "Default")
      (node (ref "X2") (pin "4") (pinfunction "4_4") (pintype "passive"))
    )
  )
)
